# Mainboard.net
KiCad netlist of a schematic drawn in EAGLE
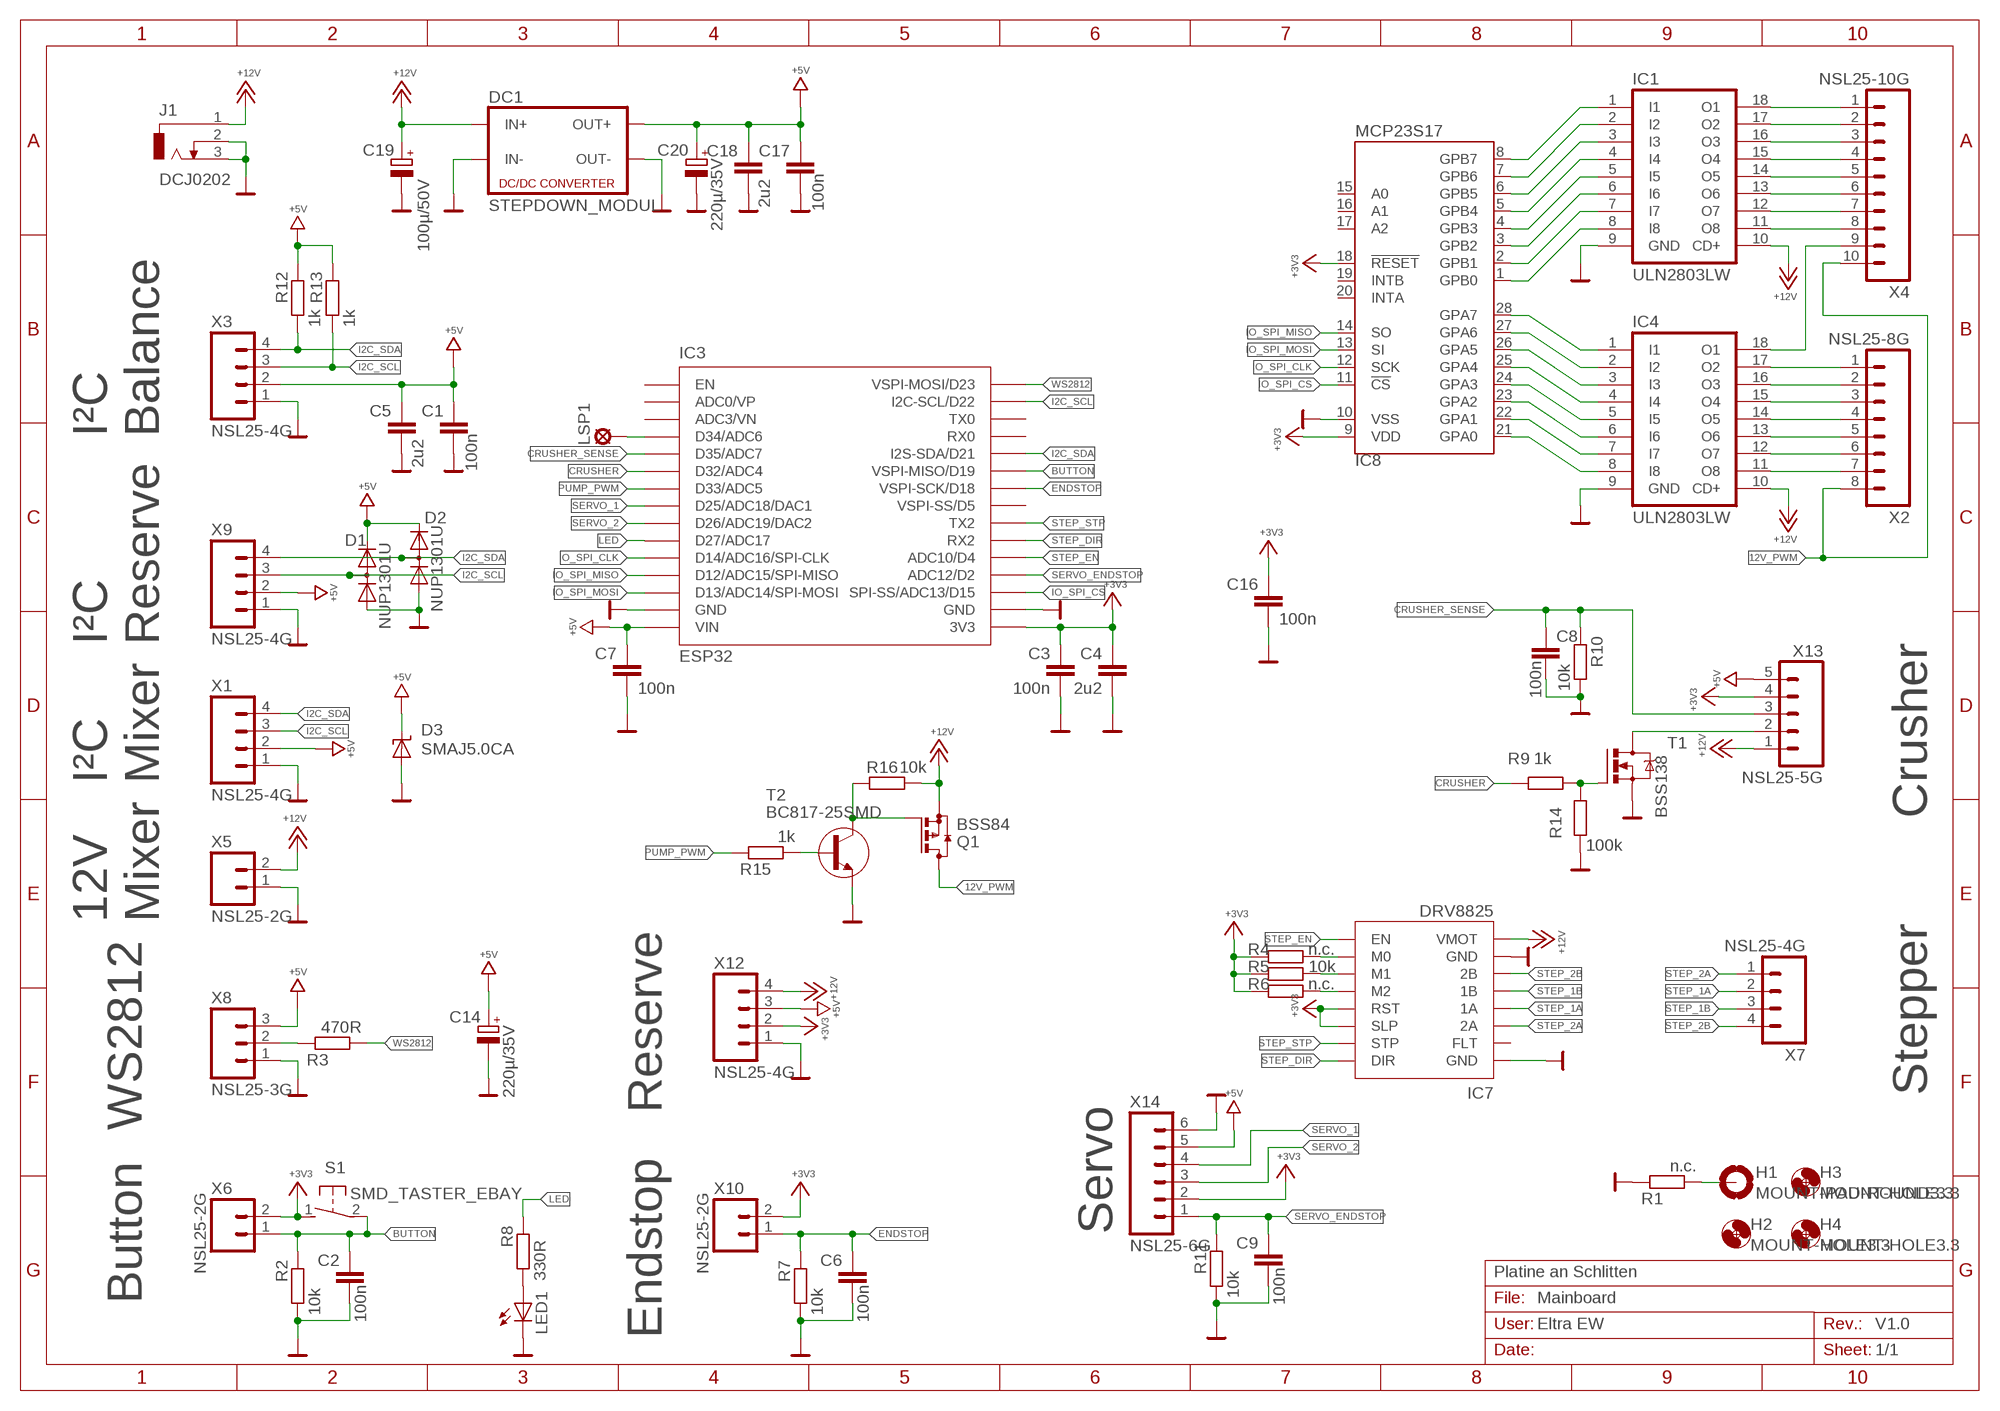
[diagram p0: schematic, sheet 1]

(export (version "E")
  (design (tool "Eeschema 10.0.6"))
  (components
    (comp (ref "C1")
      (value "100n")
      (footprint "eagle-import:0805CRH")
      (libsource (lib "eagle-import") (part "C-EUC0805CRH"))
    )
    (comp (ref "C2")
      (value "100n")
      (footprint "eagle-import:0805CRH")
      (libsource (lib "eagle-import") (part "C-EUC0805CRH"))
    )
    (comp (ref "C3")
      (value "100n")
      (footprint "eagle-import:0805CRH")
      (libsource (lib "eagle-import") (part "C-EUC0805CRH"))
    )
    (comp (ref "C4")
      (value "2u2")
      (footprint "eagle-import:0805CRH")
      (libsource (lib "eagle-import") (part "C-EUC0805CRH"))
    )
    (comp (ref "C5")
      (value "2u2")
      (footprint "eagle-import:0805CRH")
      (libsource (lib "eagle-import") (part "C-EUC0805CRH"))
    )
    (comp (ref "C6")
      (value "100n")
      (footprint "eagle-import:0805CRH")
      (libsource (lib "eagle-import") (part "C-EUC0805CRH"))
    )
    (comp (ref "C7")
      (value "100n")
      (footprint "eagle-import:0805CRH")
      (libsource (lib "eagle-import") (part "C-EUC0805CRH"))
    )
    (comp (ref "C8")
      (value "100n")
      (footprint "eagle-import:0805CRH")
      (libsource (lib "eagle-import") (part "C-EUC0805CRH"))
    )
    (comp (ref "C9")
      (value "100n")
      (footprint "eagle-import:0805CRH")
      (libsource (lib "eagle-import") (part "C-EUC0805CRH"))
    )
    (comp (ref "C14")
      (value "220µ/35V")
      (footprint "eagle-import:153CLV-1010")
      (libsource (lib "eagle-import") (part "CPOL-EU153CLV-1010"))
    )
    (comp (ref "C16")
      (value "100n")
      (footprint "eagle-import:0805CRH")
      (libsource (lib "eagle-import") (part "C-EUC0805CRH"))
    )
    (comp (ref "C17")
      (value "100n")
      (footprint "eagle-import:0805CRH")
      (libsource (lib "eagle-import") (part "C-EUC0805CRH"))
    )
    (comp (ref "C18")
      (value "2u2")
      (footprint "eagle-import:0805CRH")
      (libsource (lib "eagle-import") (part "C-EUC0805CRH"))
    )
    (comp (ref "C19")
      (value "100µ/50V")
      (footprint "eagle-import:153CLV-1010")
      (libsource (lib "eagle-import") (part "CPOL-EU153CLV-1010"))
    )
    (comp (ref "C20")
      (value "220µ/35V")
      (footprint "eagle-import:153CLV-1010")
      (libsource (lib "eagle-import") (part "CPOL-EU153CLV-1010"))
    )
    (comp (ref "D1")
      (value "NUP1301U")
      (footprint "eagle-import:SOT323-3")
      (libsource (lib "eagle-import") (part "NUP1301U_115"))
    )
    (comp (ref "D2")
      (value "NUP1301U")
      (footprint "eagle-import:SOT323-3")
      (libsource (lib "eagle-import") (part "NUP1301U_115"))
    )
    (comp (ref "D3")
      (value "SMAJ5.0CA")
      (footprint "eagle-import:SMA-DO214AC")
      (libsource (lib "eagle-import") (part "SMAJ"))
    )
    (comp (ref "DC1")
      (value "STEPDOWN_MODUL")
      (footprint "eagle-import:STEPDOWN_MODUL")
      (libsource (lib "eagle-import") (part "STEPDOWN_MODUL"))
    )
    (comp (ref "H1")
      (value "MOUNT-PAD-ROUND3.3")
      (footprint "eagle-import:3,3-PAD")
      (libsource (lib "eagle-import") (part "MOUNT-PAD-ROUND3.3"))
    )
    (comp (ref "H2")
      (value "MOUNT-HOLE3.3")
      (footprint "eagle-import:3,3")
      (libsource (lib "eagle-import") (part "MOUNT-HOLE3.3"))
    )
    (comp (ref "H3")
      (value "MOUNT-HOLE3.3")
      (footprint "eagle-import:3,3")
      (libsource (lib "eagle-import") (part "MOUNT-HOLE3.3"))
    )
    (comp (ref "H4")
      (value "MOUNT-HOLE3.3")
      (footprint "eagle-import:3,3")
      (libsource (lib "eagle-import") (part "MOUNT-HOLE3.3"))
    )
    (comp (ref "IC1")
      (value "ULN2803LW")
      (footprint "eagle-import:SO18W")
      (libsource (lib "eagle-import") (part "ULN2803LW"))
    )
    (comp (ref "IC3")
      (value "ESP32")
      (footprint "eagle-import:ESP32")
      (libsource (lib "eagle-import") (part "ESP32"))
    )
    (comp (ref "IC4")
      (value "ULN2803LW")
      (footprint "eagle-import:SO18W")
      (libsource (lib "eagle-import") (part "ULN2803LW"))
    )
    (comp (ref "IC7")
      (value "DRV8825")
      (footprint "eagle-import:DRV8825")
      (libsource (lib "eagle-import") (part "DRV8825"))
    )
    (comp (ref "IC8")
      (value "MCP23S17")
      (footprint "eagle-import:SOIC-28")
      (libsource (lib "eagle-import") (part "MCP23S17"))
    )
    (comp (ref "J1")
      (value "DCJ0202")
      (footprint "eagle-import:DCJ0202")
      (libsource (lib "eagle-import") (part "DCJ0202"))
    )
    (comp (ref "LED1")
      (value "LEDCHIPLED_0805")
      (footprint "eagle-import:CHIPLED_0805")
      (libsource (lib "eagle-import") (part "LEDCHIPLED_0805"))
    )
    (comp (ref "LSP1")
      (value "LSP06")
      (footprint "eagle-import:LSP06")
      (libsource (lib "eagle-import") (part "LSP06"))
    )
    (comp (ref "Q1")
      (value "BSS84")
      (footprint "eagle-import:SOT23")
      (libsource (lib "eagle-import") (part "BSS84"))
    )
    (comp (ref "R1")
      (value "n.c.")
      (footprint "eagle-import:0805CRH")
      (libsource (lib "eagle-import") (part "R-EU_R0805CRH"))
    )
    (comp (ref "R2")
      (value "10k")
      (footprint "eagle-import:0805CRH")
      (libsource (lib "eagle-import") (part "R-EU_R0805CRH"))
    )
    (comp (ref "R3")
      (value "470R")
      (footprint "eagle-import:0805CRH")
      (libsource (lib "eagle-import") (part "R-EU_R0805CRH"))
    )
    (comp (ref "R4")
      (value "n.c.")
      (footprint "eagle-import:0805CRH")
      (libsource (lib "eagle-import") (part "R-EU_R0805CRH"))
    )
    (comp (ref "R5")
      (value "10k")
      (footprint "eagle-import:0805CRH")
      (libsource (lib "eagle-import") (part "R-EU_R0805CRH"))
    )
    (comp (ref "R6")
      (value "n.c.")
      (footprint "eagle-import:0805CRH")
      (libsource (lib "eagle-import") (part "R-EU_R0805CRH"))
    )
    (comp (ref "R7")
      (value "10k")
      (footprint "eagle-import:0805CRH")
      (libsource (lib "eagle-import") (part "R-EU_R0805CRH"))
    )
    (comp (ref "R8")
      (value "330R")
      (footprint "eagle-import:0805CRH")
      (libsource (lib "eagle-import") (part "R-EU_R0805CRH"))
    )
    (comp (ref "R9")
      (value "1k")
      (footprint "eagle-import:0805CRH")
      (libsource (lib "eagle-import") (part "R-EU_R0805CRH"))
    )
    (comp (ref "R10")
      (value "10k")
      (footprint "eagle-import:0805CRH")
      (libsource (lib "eagle-import") (part "R-EU_R0805CRH"))
    )
    (comp (ref "R11")
      (value "10k")
      (footprint "eagle-import:0805CRH")
      (libsource (lib "eagle-import") (part "R-EU_R0805CRH"))
    )
    (comp (ref "R12")
      (value "1k")
      (footprint "eagle-import:0805CRH")
      (libsource (lib "eagle-import") (part "R-EU_R0805CRH"))
    )
    (comp (ref "R13")
      (value "1k")
      (footprint "eagle-import:0805CRH")
      (libsource (lib "eagle-import") (part "R-EU_R0805CRH"))
    )
    (comp (ref "R14")
      (value "100k")
      (footprint "eagle-import:0805CRH")
      (libsource (lib "eagle-import") (part "R-EU_R0805CRH"))
    )
    (comp (ref "R15")
      (value "1k")
      (footprint "eagle-import:0805CRH")
      (libsource (lib "eagle-import") (part "R-EU_R0805CRH"))
    )
    (comp (ref "R16")
      (value "10k")
      (footprint "eagle-import:0805CRH")
      (libsource (lib "eagle-import") (part "R-EU_R0805CRH"))
    )
    (comp (ref "S1")
      (value "SMD_TASTER_EBAY")
      (footprint "eagle-import:DTSM3XN")
      (libsource (lib "eagle-import") (part "SMD_TASTER_EBAY"))
    )
    (comp (ref "T1")
      (value "BSS138")
      (footprint "eagle-import:SOT23")
      (libsource (lib "eagle-import") (part "BSS138"))
    )
    (comp (ref "T2")
      (value "BC817-25SMD")
      (footprint "eagle-import:SOT23-BEC")
      (libsource (lib "eagle-import") (part "BC817SMD-25"))
    )
    (comp (ref "X1")
      (value "NSL25-4G")
      (footprint "eagle-import:NSL25-4G")
      (libsource (lib "eagle-import") (part "NSL25-4G"))
    )
    (comp (ref "X2")
      (value "NSL25-8G")
      (footprint "eagle-import:NSL25-8G")
      (libsource (lib "eagle-import") (part "NSL25-8G"))
    )
    (comp (ref "X3")
      (value "NSL25-4G")
      (footprint "eagle-import:NSL25-4G")
      (libsource (lib "eagle-import") (part "NSL25-4G"))
    )
    (comp (ref "X4")
      (value "NSL25-10G")
      (footprint "eagle-import:NSL25-10G")
      (libsource (lib "eagle-import") (part "NSL25-10G"))
    )
    (comp (ref "X5")
      (value "NSL25-2G")
      (footprint "eagle-import:NSL25-2G")
      (libsource (lib "eagle-import") (part "NSL25-2G"))
    )
    (comp (ref "X6")
      (value "NSL25-2G")
      (footprint "eagle-import:NSL25-2G")
      (libsource (lib "eagle-import") (part "NSL25-2G"))
    )
    (comp (ref "X7")
      (value "NSL25-4G")
      (footprint "eagle-import:NSL25-4G")
      (libsource (lib "eagle-import") (part "NSL25-4G"))
    )
    (comp (ref "X8")
      (value "NSL25-3G")
      (footprint "eagle-import:NSL25-3G")
      (libsource (lib "eagle-import") (part "NSL25-3G"))
    )
    (comp (ref "X9")
      (value "NSL25-4G")
      (footprint "eagle-import:NSL25-4G")
      (libsource (lib "eagle-import") (part "NSL25-4G"))
    )
    (comp (ref "X10")
      (value "NSL25-2G")
      (footprint "eagle-import:NSL25-2G")
      (libsource (lib "eagle-import") (part "NSL25-2G"))
    )
    (comp (ref "X12")
      (value "NSL25-4G")
      (footprint "eagle-import:NSL25-4G")
      (libsource (lib "eagle-import") (part "NSL25-4G"))
    )
    (comp (ref "X13")
      (value "NSL25-5G")
      (footprint "eagle-import:NSL25-5G")
      (libsource (lib "eagle-import") (part "NSL25-5G"))
    )
    (comp (ref "X14")
      (value "NSL25-6G")
      (footprint "eagle-import:NSL25-6G")
      (libsource (lib "eagle-import") (part "NSL25-6G"))
    )
  )
  (nets
    (net (code "1") (name "+3V3") (class "Default")
      (node (ref "C16") (pin "1") (pinfunction "1_1") (pintype "passive"))
      (node (ref "C3") (pin "1") (pinfunction "1_1") (pintype "passive"))
      (node (ref "C4") (pin "1") (pinfunction "1_1") (pintype "passive"))
      (node (ref "IC3") (pin "3V3") (pinfunction "3V3_3V3") (pintype "power_in"))
      (node (ref "IC7") (pin "RST") (pinfunction "RST_RST") (pintype "bidirectional"))
      (node (ref "IC7") (pin "SLP") (pinfunction "SLP_SLP") (pintype "bidirectional"))
      (node (ref "IC8") (pin "18") (pinfunction "~{RESET}_18") (pintype "input"))
      (node (ref "IC8") (pin "9") (pinfunction "VDD_9") (pintype "power_in"))
      (node (ref "R4") (pin "1") (pinfunction "1_1") (pintype "passive"))
      (node (ref "R5") (pin "1") (pinfunction "1_1") (pintype "passive"))
      (node (ref "R6") (pin "1") (pinfunction "1_1") (pintype "passive"))
      (node (ref "S1") (pin "1") (pinfunction "S_1") (pintype "passive"))
      (node (ref "X10") (pin "2") (pinfunction "2_2") (pintype "passive"))
      (node (ref "X12") (pin "2") (pinfunction "2_2") (pintype "passive"))
      (node (ref "X13") (pin "4") (pinfunction "4_4") (pintype "passive"))
      (node (ref "X14") (pin "2") (pinfunction "2_2") (pintype "passive"))
      (node (ref "X6") (pin "2") (pinfunction "2_2") (pintype "passive"))
    )
    (net (code "2") (name "+5V") (class "Default")
      (node (ref "C1") (pin "1") (pinfunction "1_1") (pintype "passive"))
      (node (ref "C14") (pin "+") (pinfunction "+_+") (pintype "passive"))
      (node (ref "C17") (pin "1") (pinfunction "1_1") (pintype "passive"))
      (node (ref "C18") (pin "1") (pinfunction "1_1") (pintype "passive"))
      (node (ref "C20") (pin "+") (pinfunction "+_+") (pintype "passive"))
      (node (ref "C5") (pin "1") (pinfunction "1_1") (pintype "passive"))
      (node (ref "C7") (pin "1") (pinfunction "1_1") (pintype "passive"))
      (node (ref "D1") (pin "2") (pinfunction "2_2") (pintype "passive"))
      (node (ref "D2") (pin "2") (pinfunction "2_2") (pintype "passive"))
      (node (ref "D3") (pin "K") (pinfunction "C_K") (pintype "passive"))
      (node (ref "DC1") (pin "OUT+") (pinfunction "OUT+_OUT+") (pintype "passive"))
      (node (ref "IC3") (pin "VIN") (pinfunction "VIN_VIN") (pintype "power_in"))
      (node (ref "R12") (pin "1") (pinfunction "1_1") (pintype "passive"))
      (node (ref "R13") (pin "1") (pinfunction "1_1") (pintype "passive"))
      (node (ref "X1") (pin "2") (pinfunction "2_2") (pintype "passive"))
      (node (ref "X12") (pin "3") (pinfunction "3_3") (pintype "passive"))
      (node (ref "X13") (pin "5") (pinfunction "5_5") (pintype "passive"))
      (node (ref "X14") (pin "5") (pinfunction "5_5") (pintype "passive"))
      (node (ref "X3") (pin "2") (pinfunction "2_2") (pintype "passive"))
      (node (ref "X8") (pin "3") (pinfunction "3_3") (pintype "passive"))
      (node (ref "X9") (pin "2") (pinfunction "2_2") (pintype "passive"))
    )
    (net (code "3") (name "+12V") (class "Default")
      (node (ref "C19") (pin "+") (pinfunction "+_+") (pintype "passive"))
      (node (ref "DC1") (pin "IN+") (pinfunction "IN+_IN+") (pintype "passive"))
      (node (ref "IC1") (pin "10") (pinfunction "CD+_10") (pintype "passive"))
      (node (ref "IC4") (pin "10") (pinfunction "CD+_10") (pintype "passive"))
      (node (ref "IC7") (pin "VMOT") (pinfunction "VMOT_VMOT") (pintype "power_in"))
      (node (ref "J1") (pin "1") (pinfunction "1_1") (pintype "passive"))
      (node (ref "Q1") (pin "2") (pinfunction "S_2") (pintype "passive"))
      (node (ref "R16") (pin "2") (pinfunction "2_2") (pintype "passive"))
      (node (ref "X12") (pin "4") (pinfunction "4_4") (pintype "passive"))
      (node (ref "X13") (pin "1") (pinfunction "1_1") (pintype "passive"))
      (node (ref "X5") (pin "2") (pinfunction "2_2") (pintype "passive"))
    )
    (net (code "4") (name "/ADC3{slash}VN") (class "Default")
      (node (ref "IC3") (pin "VN") (pinfunction "ADC3/VN_VN") (pintype "power_in"))
    )
    (net (code "5") (name "12V_PWM") (class "Default")
      (node (ref "Q1") (pin "3") (pinfunction "D_3") (pintype "passive"))
      (node (ref "X2") (pin "8") (pinfunction "8_8") (pintype "passive"))
      (node (ref "X4") (pin "10") (pinfunction "10_10") (pintype "passive"))
    )
    (net (code "6") (name "BUTTON") (class "Default")
      (node (ref "C2") (pin "1") (pinfunction "1_1") (pintype "passive"))
      (node (ref "IC3") (pin "D19") (pinfunction "VSPI-MISO/D19_D19") (pintype "bidirectional"))
      (node (ref "R2") (pin "1") (pinfunction "1_1") (pintype "passive"))
      (node (ref "S1") (pin "2") (pinfunction "P_2") (pintype "passive"))
      (node (ref "X6") (pin "1") (pinfunction "1_1") (pintype "passive"))
    )
    (net (code "7") (name "CRUSHER") (class "Default")
      (node (ref "IC3") (pin "D32") (pinfunction "D32/ADC4_D32") (pintype "power_in"))
      (node (ref "R9") (pin "1") (pinfunction "1_1") (pintype "passive"))
    )
    (net (code "8") (name "CRUSHER_SENSE") (class "Default")
      (node (ref "C8") (pin "1") (pinfunction "1_1") (pintype "passive"))
      (node (ref "IC3") (pin "D35") (pinfunction "D35/ADC7_D35") (pintype "bidirectional"))
      (node (ref "R10") (pin "1") (pinfunction "1_1") (pintype "passive"))
      (node (ref "X13") (pin "3") (pinfunction "3_3") (pintype "passive"))
    )
    (net (code "9") (name "ENDSTOP") (class "Default")
      (node (ref "C6") (pin "1") (pinfunction "1_1") (pintype "passive"))
      (node (ref "IC3") (pin "D18") (pinfunction "VSPI-SCK/D18_D18") (pintype "bidirectional"))
      (node (ref "R7") (pin "1") (pinfunction "1_1") (pintype "passive"))
      (node (ref "X10") (pin "1") (pinfunction "1_1") (pintype "passive"))
    )
    (net (code "10") (name "GND") (class "Default")
      (node (ref "C1") (pin "2") (pinfunction "2_2") (pintype "passive"))
      (node (ref "C14") (pin "-") (pinfunction "-_-") (pintype "passive"))
      (node (ref "C16") (pin "2") (pinfunction "2_2") (pintype "passive"))
      (node (ref "C17") (pin "2") (pinfunction "2_2") (pintype "passive"))
      (node (ref "C18") (pin "2") (pinfunction "2_2") (pintype "passive"))
      (node (ref "C19") (pin "-") (pinfunction "-_-") (pintype "passive"))
      (node (ref "C2") (pin "2") (pinfunction "2_2") (pintype "passive"))
      (node (ref "C20") (pin "-") (pinfunction "-_-") (pintype "passive"))
      (node (ref "C3") (pin "2") (pinfunction "2_2") (pintype "passive"))
      (node (ref "C4") (pin "2") (pinfunction "2_2") (pintype "passive"))
      (node (ref "C5") (pin "2") (pinfunction "2_2") (pintype "passive"))
      (node (ref "C6") (pin "2") (pinfunction "2_2") (pintype "passive"))
      (node (ref "C7") (pin "2") (pinfunction "2_2") (pintype "passive"))
      (node (ref "C8") (pin "2") (pinfunction "2_2") (pintype "passive"))
      (node (ref "C9") (pin "2") (pinfunction "2_2") (pintype "passive"))
      (node (ref "D1") (pin "1") (pinfunction "1_1") (pintype "passive"))
      (node (ref "D2") (pin "1") (pinfunction "1_1") (pintype "passive"))
      (node (ref "D3") (pin "A") (pinfunction "A_A") (pintype "passive"))
      (node (ref "DC1") (pin "IN-") (pinfunction "IN-_IN-") (pintype "passive"))
      (node (ref "DC1") (pin "OUT-") (pinfunction "OUT-_OUT-") (pintype "passive"))
      (node (ref "IC1") (pin "9") (pinfunction "GND_9") (pintype "power_in"))
      (node (ref "IC3") (pin "GND@1") (pinfunction "GND_GND@1") (pintype "power_in"))
      (node (ref "IC3") (pin "GND@2") (pinfunction "GND_GND@2") (pintype "power_in"))
      (node (ref "IC4") (pin "9") (pinfunction "GND_9") (pintype "power_in"))
      (node (ref "IC7") (pin "GND@1") (pinfunction "GND_GND@1") (pintype "power_in"))
      (node (ref "IC7") (pin "GND@2") (pinfunction "GND_GND@2") (pintype "power_in"))
      (node (ref "IC8") (pin "10") (pinfunction "VSS_10") (pintype "power_in"))
      (node (ref "J1") (pin "2") (pinfunction "2_2") (pintype "passive"))
      (node (ref "J1") (pin "3") (pinfunction "3_3") (pintype "passive"))
      (node (ref "LED1") (pin "C") (pinfunction "C_C") (pintype "passive"))
      (node (ref "R1") (pin "1") (pinfunction "1_1") (pintype "passive"))
      (node (ref "R10") (pin "2") (pinfunction "2_2") (pintype "passive"))
      (node (ref "R11") (pin "2") (pinfunction "2_2") (pintype "passive"))
      (node (ref "R14") (pin "1") (pinfunction "1_1") (pintype "passive"))
      (node (ref "R2") (pin "2") (pinfunction "2_2") (pintype "passive"))
      (node (ref "R7") (pin "2") (pinfunction "2_2") (pintype "passive"))
      (node (ref "T1") (pin "2") (pinfunction "S_2") (pintype "passive"))
      (node (ref "T2") (pin "E") (pinfunction "E_E") (pintype "passive"))
      (node (ref "X1") (pin "1") (pinfunction "1_1") (pintype "passive"))
      (node (ref "X12") (pin "1") (pinfunction "1_1") (pintype "passive"))
      (node (ref "X14") (pin "6") (pinfunction "6_6") (pintype "passive"))
      (node (ref "X3") (pin "1") (pinfunction "1_1") (pintype "passive"))
      (node (ref "X5") (pin "1") (pinfunction "1_1") (pintype "passive"))
      (node (ref "X8") (pin "1") (pinfunction "1_1") (pintype "passive"))
      (node (ref "X9") (pin "1") (pinfunction "1_1") (pintype "passive"))
    )
    (net (code "11") (name "I2C_SCL") (class "Default")
      (node (ref "D1") (pin "3") (pinfunction "3_3") (pintype "passive"))
      (node (ref "IC3") (pin "D22") (pinfunction "I2C-SCL/D22_D22") (pintype "bidirectional"))
      (node (ref "R13") (pin "2") (pinfunction "2_2") (pintype "passive"))
      (node (ref "X1") (pin "3") (pinfunction "3_3") (pintype "passive"))
      (node (ref "X3") (pin "3") (pinfunction "3_3") (pintype "passive"))
      (node (ref "X9") (pin "3") (pinfunction "3_3") (pintype "passive"))
    )
    (net (code "12") (name "I2C_SDA") (class "Default")
      (node (ref "D2") (pin "3") (pinfunction "3_3") (pintype "passive"))
      (node (ref "IC3") (pin "D21") (pinfunction "I2S-SDA/D21_D21") (pintype "bidirectional"))
      (node (ref "R12") (pin "2") (pinfunction "2_2") (pintype "passive"))
      (node (ref "X1") (pin "4") (pinfunction "4_4") (pintype "passive"))
      (node (ref "X3") (pin "4") (pinfunction "4_4") (pintype "passive"))
      (node (ref "X9") (pin "4") (pinfunction "4_4") (pintype "passive"))
    )
    (net (code "13") (name "IO_SPI_CLK") (class "Default")
      (node (ref "IC3") (pin "D14") (pinfunction "D14/ADC16/SPI-CLK_D14") (pintype "bidirectional"))
      (node (ref "IC8") (pin "12") (pinfunction "SCK_12") (pintype "input"))
    )
    (net (code "14") (name "IO_SPI_CS") (class "Default")
      (node (ref "IC3") (pin "D15") (pinfunction "SPI-SS/ADC13/D15_D15") (pintype "bidirectional"))
      (node (ref "IC8") (pin "11") (pinfunction "~{CS}_11") (pintype "input"))
    )
    (net (code "15") (name "IO_SPI_MISO") (class "Default")
      (node (ref "IC3") (pin "D12") (pinfunction "D12/ADC15/SPI-MISO_D12") (pintype "bidirectional"))
      (node (ref "IC8") (pin "14") (pinfunction "SO_14") (pintype "input"))
    )
    (net (code "16") (name "IO_SPI_MOSI") (class "Default")
      (node (ref "IC3") (pin "D13") (pinfunction "D13/ADC14/SPI-MOSI_D13") (pintype "power_in"))
      (node (ref "IC8") (pin "13") (pinfunction "SI_13") (pintype "input"))
    )
    (net (code "17") (name "LED") (class "Default")
      (node (ref "IC3") (pin "D27") (pinfunction "D27/ADC17_D27") (pintype "bidirectional"))
      (node (ref "R8") (pin "1") (pinfunction "1_1") (pintype "passive"))
    )
    (net (code "18") (name "Net-(H1-MOUNT)") (class "Default")
      (node (ref "H1") (pin "B3,3") (pinfunction "MOUNT_B3,3") (pintype "passive"))
      (node (ref "R1") (pin "2") (pinfunction "2_2") (pintype "passive"))
    )
    (net (code "19") (name "Net-(IC1-I1)") (class "Default")
      (node (ref "IC1") (pin "1") (pinfunction "I1_1") (pintype "input"))
      (node (ref "IC8") (pin "8") (pinfunction "GPB7_8") (pintype "open_collector"))
    )
    (net (code "20") (name "Net-(IC1-I2)") (class "Default")
      (node (ref "IC1") (pin "2") (pinfunction "I2_2") (pintype "input"))
      (node (ref "IC8") (pin "7") (pinfunction "GPB6_7") (pintype "open_collector"))
    )
    (net (code "21") (name "Net-(IC1-I3)") (class "Default")
      (node (ref "IC1") (pin "3") (pinfunction "I3_3") (pintype "input"))
      (node (ref "IC8") (pin "6") (pinfunction "GPB5_6") (pintype "open_collector"))
    )
    (net (code "22") (name "Net-(IC1-I4)") (class "Default")
      (node (ref "IC1") (pin "4") (pinfunction "I4_4") (pintype "input"))
      (node (ref "IC8") (pin "5") (pinfunction "GPB4_5") (pintype "open_collector"))
    )
    (net (code "23") (name "Net-(IC1-I5)") (class "Default")
      (node (ref "IC1") (pin "5") (pinfunction "I5_5") (pintype "input"))
      (node (ref "IC8") (pin "4") (pinfunction "GPB3_4") (pintype "open_collector"))
    )
    (net (code "24") (name "Net-(IC1-I6)") (class "Default")
      (node (ref "IC1") (pin "6") (pinfunction "I6_6") (pintype "input"))
      (node (ref "IC8") (pin "3") (pinfunction "GPB2_3") (pintype "open_collector"))
    )
    (net (code "25") (name "Net-(IC1-I7)") (class "Default")
      (node (ref "IC1") (pin "7") (pinfunction "I7_7") (pintype "input"))
      (node (ref "IC8") (pin "2") (pinfunction "GPB1_2") (pintype "open_collector"))
    )
    (net (code "26") (name "Net-(IC1-I8)") (class "Default")
      (node (ref "IC1") (pin "8") (pinfunction "I8_8") (pintype "input"))
      (node (ref "IC8") (pin "1") (pinfunction "GPB0_1") (pintype "open_collector"))
    )
    (net (code "27") (name "Net-(IC1-O1)") (class "Default")
      (node (ref "IC1") (pin "18") (pinfunction "O1_18") (pintype "open_collector"))
      (node (ref "X4") (pin "1") (pinfunction "1_1") (pintype "passive"))
    )
    (net (code "28") (name "Net-(IC1-O2)") (class "Default")
      (node (ref "IC1") (pin "17") (pinfunction "O2_17") (pintype "open_collector"))
      (node (ref "X4") (pin "2") (pinfunction "2_2") (pintype "passive"))
    )
    (net (code "29") (name "Net-(IC1-O3)") (class "Default")
      (node (ref "IC1") (pin "16") (pinfunction "O3_16") (pintype "open_collector"))
      (node (ref "X4") (pin "3") (pinfunction "3_3") (pintype "passive"))
    )
    (net (code "30") (name "Net-(IC1-O4)") (class "Default")
      (node (ref "IC1") (pin "15") (pinfunction "O4_15") (pintype "open_collector"))
      (node (ref "X4") (pin "4") (pinfunction "4_4") (pintype "passive"))
    )
    (net (code "31") (name "Net-(IC1-O5)") (class "Default")
      (node (ref "IC1") (pin "14") (pinfunction "O5_14") (pintype "open_collector"))
      (node (ref "X4") (pin "5") (pinfunction "5_5") (pintype "passive"))
    )
    (net (code "32") (name "Net-(IC1-O6)") (class "Default")
      (node (ref "IC1") (pin "13") (pinfunction "O6_13") (pintype "open_collector"))
      (node (ref "X4") (pin "6") (pinfunction "6_6") (pintype "passive"))
    )
    (net (code "33") (name "Net-(IC1-O7)") (class "Default")
      (node (ref "IC1") (pin "12") (pinfunction "O7_12") (pintype "open_collector"))
      (node (ref "X4") (pin "7") (pinfunction "7_7") (pintype "passive"))
    )
    (net (code "34") (name "Net-(IC1-O8)") (class "Default")
      (node (ref "IC1") (pin "11") (pinfunction "O8_11") (pintype "open_collector"))
      (node (ref "X4") (pin "8") (pinfunction "8_8") (pintype "passive"))
    )
    (net (code "35") (name "Net-(IC3-D34{slash}ADC6)") (class "Default")
      (node (ref "IC3") (pin "D34") (pinfunction "D34/ADC6_D34") (pintype "bidirectional"))
      (node (ref "LSP1") (pin "MP") (pinfunction "MP_MP") (pintype "passive"))
    )
    (net (code "36") (name "Net-(IC4-I1)") (class "Default")
      (node (ref "IC4") (pin "1") (pinfunction "I1_1") (pintype "input"))
      (node (ref "IC8") (pin "28") (pinfunction "GPA7_28") (pintype "open_collector"))
    )
    (net (code "37") (name "Net-(IC4-I2)") (class "Default")
      (node (ref "IC4") (pin "2") (pinfunction "I2_2") (pintype "input"))
      (node (ref "IC8") (pin "27") (pinfunction "GPA6_27") (pintype "open_collector"))
    )
    (net (code "38") (name "Net-(IC4-I3)") (class "Default")
      (node (ref "IC4") (pin "3") (pinfunction "I3_3") (pintype "input"))
      (node (ref "IC8") (pin "26") (pinfunction "GPA5_26") (pintype "open_collector"))
    )
    (net (code "39") (name "Net-(IC4-I4)") (class "Default")
      (node (ref "IC4") (pin "4") (pinfunction "I4_4") (pintype "input"))
      (node (ref "IC8") (pin "25") (pinfunction "GPA4_25") (pintype "open_collector"))
    )
    (net (code "40") (name "Net-(IC4-I5)") (class "Default")
      (node (ref "IC4") (pin "5") (pinfunction "I5_5") (pintype "input"))
      (node (ref "IC8") (pin "24") (pinfunction "GPA3_24") (pintype "open_collector"))
    )
    (net (code "41") (name "Net-(IC4-I6)") (class "Default")
      (node (ref "IC4") (pin "6") (pinfunction "I6_6") (pintype "input"))
      (node (ref "IC8") (pin "23") (pinfunction "GPA2_23") (pintype "open_collector"))
    )
    (net (code "42") (name "Net-(IC4-I7)") (class "Default")
      (node (ref "IC4") (pin "7") (pinfunction "I7_7") (pintype "input"))
      (node (ref "IC8") (pin "22") (pinfunction "GPA1_22") (pintype "open_collector"))
    )
    (net (code "43") (name "Net-(IC4-I8)") (class "Default")
      (node (ref "IC4") (pin "8") (pinfunction "I8_8") (pintype "input"))
      (node (ref "IC8") (pin "21") (pinfunction "GPA0_21") (pintype "open_collector"))
    )
    (net (code "44") (name "Net-(IC4-O1)") (class "Default")
      (node (ref "IC4") (pin "18") (pinfunction "O1_18") (pintype "open_collector"))
      (node (ref "X4") (pin "9") (pinfunction "9_9") (pintype "passive"))
    )
    (net (code "45") (name "Net-(IC4-O2)") (class "Default")
      (node (ref "IC4") (pin "17") (pinfunction "O2_17") (pintype "open_collector"))
      (node (ref "X2") (pin "1") (pinfunction "1_1") (pintype "passive"))
    )
    (net (code "46") (name "Net-(IC4-O3)") (class "Default")
      (node (ref "IC4") (pin "16") (pinfunction "O3_16") (pintype "open_collector"))
      (node (ref "X2") (pin "2") (pinfunction "2_2") (pintype "passive"))
    )
    (net (code "47") (name "Net-(IC4-O4)") (class "Default")
      (node (ref "IC4") (pin "15") (pinfunction "O4_15") (pintype "open_collector"))
      (node (ref "X2") (pin "3") (pinfunction "3_3") (pintype "passive"))
    )
    (net (code "48") (name "Net-(IC4-O5)") (class "Default")
      (node (ref "IC4") (pin "14") (pinfunction "O5_14") (pintype "open_collector"))
      (node (ref "X2") (pin "4") (pinfunction "4_4") (pintype "passive"))
    )
    (net (code "49") (name "Net-(IC4-O6)") (class "Default")
      (node (ref "IC4") (pin "13") (pinfunction "O6_13") (pintype "open_collector"))
      (node (ref "X2") (pin "5") (pinfunction "5_5") (pintype "passive"))
    )
    (net (code "50") (name "Net-(IC4-O7)") (class "Default")
      (node (ref "IC4") (pin "12") (pinfunction "O7_12") (pintype "open_collector"))
      (node (ref "X2") (pin "6") (pinfunction "6_6") (pintype "passive"))
    )
    (net (code "51") (name "Net-(IC4-O8)") (class "Default")
      (node (ref "IC4") (pin "11") (pinfunction "O8_11") (pintype "open_collector"))
      (node (ref "X2") (pin "7") (pinfunction "7_7") (pintype "passive"))
    )
    (net (code "52") (name "Net-(IC7-PadM0)") (class "Default")
      (node (ref "IC7") (pin "M0") (pinfunction "M0_M0") (pintype "bidirectional"))
      (node (ref "R4") (pin "2") (pinfunction "2_2") (pintype "passive"))
    )
    (net (code "53") (name "Net-(IC7-PadM1)") (class "Default")
      (node (ref "IC7") (pin "M1") (pinfunction "M1_M1") (pintype "bidirectional"))
      (node (ref "R5") (pin "2") (pinfunction "2_2") (pintype "passive"))
    )
    (net (code "54") (name "Net-(IC7-PadM2)") (class "Default")
      (node (ref "IC7") (pin "M2") (pinfunction "M2_M2") (pintype "bidirectional"))
      (node (ref "R6") (pin "2") (pinfunction "2_2") (pintype "passive"))
    )
    (net (code "55") (name "Net-(LED1-PadA)") (class "Default")
      (node (ref "LED1") (pin "A") (pinfunction "A_A") (pintype "passive"))
      (node (ref "R8") (pin "2") (pinfunction "2_2") (pintype "passive"))
    )
    (net (code "56") (name "Net-(Q1-G)") (class "Default")
      (node (ref "Q1") (pin "1") (pinfunction "G_1") (pintype "passive"))
      (node (ref "R16") (pin "1") (pinfunction "1_1") (pintype "passive"))
      (node (ref "T2") (pin "C") (pinfunction "C_C") (pintype "passive"))
    )
    (net (code "57") (name "Net-(R3-Pad1)") (class "Default")
      (node (ref "R3") (pin "1") (pinfunction "1_1") (pintype "passive"))
      (node (ref "X8") (pin "2") (pinfunction "2_2") (pintype "passive"))
    )
    (net (code "58") (name "Net-(R15-Pad2)") (class "Default")
      (node (ref "R15") (pin "2") (pinfunction "2_2") (pintype "passive"))
      (node (ref "T2") (pin "B") (pinfunction "B_B") (pintype "passive"))
    )
    (net (code "59") (name "Net-(T1-D)") (class "Default")
      (node (ref "T1") (pin "3") (pinfunction "D_3") (pintype "passive"))
      (node (ref "X13") (pin "2") (pinfunction "2_2") (pintype "passive"))
    )
    (net (code "60") (name "Net-(T1-G)") (class "Default")
      (node (ref "R14") (pin "2") (pinfunction "2_2") (pintype "passive"))
      (node (ref "R9") (pin "2") (pinfunction "2_2") (pintype "passive"))
      (node (ref "T1") (pin "1") (pinfunction "G_1") (pintype "passive"))
    )
    (net (code "61") (name "PUMP_PWM") (class "Default")
      (node (ref "IC3") (pin "D33") (pinfunction "D33/ADC5_D33") (pintype "bidirectional"))
      (node (ref "R15") (pin "1") (pinfunction "1_1") (pintype "passive"))
    )
    (net (code "62") (name "SERVO_1") (class "Default")
      (node (ref "IC3") (pin "D25") (pinfunction "D25/ADC18/DAC1_D25") (pintype "bidirectional"))
      (node (ref "X14") (pin "4") (pinfunction "4_4") (pintype "passive"))
    )
    (net (code "63") (name "SERVO_2") (class "Default")
      (node (ref "IC3") (pin "D26") (pinfunction "D26/ADC19/DAC2_D26") (pintype "bidirectional"))
      (node (ref "X14") (pin "3") (pinfunction "3_3") (pintype "passive"))
    )
    (net (code "64") (name "SERVO_ENDSTOP") (class "Default")
      (node (ref "C9") (pin "1") (pinfunction "1_1") (pintype "passive"))
      (node (ref "IC3") (pin "D2") (pinfunction "ADC12/D2_D2") (pintype "bidirectional"))
      (node (ref "R11") (pin "1") (pinfunction "1_1") (pintype "passive"))
      (node (ref "X14") (pin "1") (pinfunction "1_1") (pintype "passive"))
    )
    (net (code "65") (name "STEP_1A") (class "Default")
      (node (ref "IC7") (pin "1A") (pinfunction "1A_1A") (pintype "bidirectional"))
      (node (ref "X7") (pin "2") (pinfunction "2_2") (pintype "passive"))
    )
    (net (code "66") (name "STEP_1B") (class "Default")
      (node (ref "IC7") (pin "1B") (pinfunction "1B_1B") (pintype "bidirectional"))
      (node (ref "X7") (pin "3") (pinfunction "3_3") (pintype "passive"))
    )
    (net (code "67") (name "STEP_2A") (class "Default")
      (node (ref "IC7") (pin "2A") (pinfunction "2A_2A") (pintype "bidirectional"))
      (node (ref "X7") (pin "1") (pinfunction "1_1") (pintype "passive"))
    )
    (net (code "68") (name "STEP_2B") (class "Default")
      (node (ref "IC7") (pin "2B") (pinfunction "2B_2B") (pintype "bidirectional"))
      (node (ref "X7") (pin "4") (pinfunction "4_4") (pintype "passive"))
    )
    (net (code "69") (name "STEP_DIR") (class "Default")
      (node (ref "IC3") (pin "RX2") (pinfunction "RX2_RX2") (pintype "bidirectional"))
      (node (ref "IC7") (pin "DIR") (pinfunction "DIR_DIR") (pintype "bidirectional"))
    )
    (net (code "70") (name "STEP_EN") (class "Default")
      (node (ref "IC3") (pin "D4") (pinfunction "ADC10/D4_D4") (pintype "bidirectional"))
      (node (ref "IC7") (pin "EN") (pinfunction "EN_EN") (pintype "bidirectional"))
    )
    (net (code "71") (name "STEP_STP") (class "Default")
      (node (ref "IC3") (pin "TX2") (pinfunction "TX2_TX2") (pintype "bidirectional"))
      (node (ref "IC7") (pin "STP") (pinfunction "STP_STP") (pintype "bidirectional"))
    )
    (net (code "72") (name "WS2812") (class "Default")
      (node (ref "IC3") (pin "D23") (pinfunction "VSPI-MOSI/D23_D23") (pintype "bidirectional"))
      (node (ref "R3") (pin "2") (pinfunction "2_2") (pintype "passive"))
    )
    (net (code "73") (name "unconnected-(IC3-ADC0{slash}VP-PadVP)") (class "Default")
      (node (ref "IC3") (pin "VP") (pinfunction "ADC0/VP_VP") (pintype "bidirectional"))
    )
    (net (code "74") (name "unconnected-(IC3-PadEN)") (class "Default")
      (node (ref "IC3") (pin "EN") (pinfunction "EN_EN") (pintype "bidirectional"))
    )
    (net (code "75") (name "unconnected-(IC3-PadRX0)") (class "Default")
      (node (ref "IC3") (pin "RX0") (pinfunction "RX0_RX0") (pintype "bidirectional"))
    )
    (net (code "76") (name "unconnected-(IC3-PadTX0)") (class "Default")
      (node (ref "IC3") (pin "TX0") (pinfunction "TX0_TX0") (pintype "bidirectional"))
    )
    (net (code "77") (name "unconnected-(IC3-VSPI-SS{slash}D5-PadD5)") (class "Default")
      (node (ref "IC3") (pin "D5") (pinfunction "VSPI-SS/D5_D5") (pintype "bidirectional"))
    )
    (net (code "78") (name "unconnected-(IC7-PadFLT)") (class "Default")
      (node (ref "IC7") (pin "FLT") (pinfunction "FLT_FLT") (pintype "bidirectional"))
    )
    (net (code "79") (name "unconnected-(IC8-A0-Pad15)") (class "Default")
      (node (ref "IC8") (pin "15") (pinfunction "A0_15") (pintype "input"))
    )
    (net (code "80") (name "unconnected-(IC8-A1-Pad16)") (class "Default")
      (node (ref "IC8") (pin "16") (pinfunction "A1_16") (pintype "input"))
    )
    (net (code "81") (name "unconnected-(IC8-A2-Pad17)") (class "Default")
      (node (ref "IC8") (pin "17") (pinfunction "A2_17") (pintype "input"))
    )
    (net (code "82") (name "unconnected-(IC8-INTA-Pad20)") (class "Default")
      (node (ref "IC8") (pin "20") (pinfunction "INTA_20") (pintype "input"))
    )
    (net (code "83") (name "unconnected-(IC8-INTB-Pad19)") (class "Default")
      (node (ref "IC8") (pin "19") (pinfunction "INTB_19") (pintype "input"))
    )
  )
)
